# nfc_with_data_transfer_no_accel_2_0.net
KiCad netlist of a schematic drawn in EAGLE
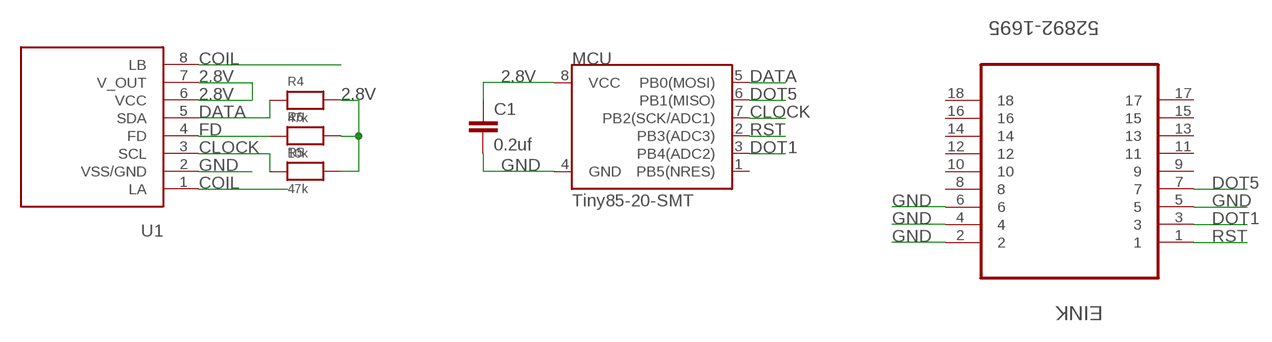
[diagram p0: schematic, sheet 1]

(export (version "E")
  (design (tool "Eeschema 10.0.6"))
  (components
    (comp (ref "C1")
      (value "0.2uf")
      (footprint "eagle-import:1206")
      (libsource (lib "eagle-import") (part "CAP1206"))
    )
    (comp (ref "EINK")
      (value "52892-1695")
      (footprint "eagle-import:MOLEX_52892-1695")
      (libsource (lib "eagle-import") (part "52892-1695"))
    )
    (comp (ref "MCU")
      (value "Tiny85-20-SMT")
      (footprint "eagle-import:SO08-EIAJ")
      (libsource (lib "eagle-import") (part "ATTINY45TINY85-20-SMT"))
    )
    (comp (ref "R4")
      (value "47k")
      (footprint "eagle-import:0603")
      (libsource (lib "eagle-import") (part "RESISTOR0603"))
    )
    (comp (ref "R5")
      (value "47k")
      (footprint "eagle-import:0603")
      (libsource (lib "eagle-import") (part "RESISTOR0603"))
    )
    (comp (ref "R6")
      (value "10k")
      (footprint "eagle-import:0603")
      (libsource (lib "eagle-import") (part "RESISTOR0603"))
    )
    (comp (ref "U1")
      (value "NT3H1101")
      (footprint "eagle-import:NT3H1101")
      (libsource (lib "eagle-import") (part "NT3H1101"))
    )
  )
  (nets
    (net (code "1") (name "/2.8V") (class "Default")
      (node (ref "C1") (pin "1") (pinfunction "1_1") (pintype "passive"))
      (node (ref "MCU") (pin "8") (pinfunction "VCC_8") (pintype "bidirectional"))
      (node (ref "R4") (pin "2") (pinfunction "2_2") (pintype "passive"))
      (node (ref "R5") (pin "2") (pinfunction "2_2") (pintype "passive"))
      (node (ref "R6") (pin "2") (pinfunction "2_2") (pintype "passive"))
      (node (ref "U1") (pin "6") (pinfunction "VCC_6") (pintype "power_in"))
      (node (ref "U1") (pin "7") (pinfunction "V_OUT_7") (pintype "power_in"))
    )
    (net (code "2") (name "/CLOCK") (class "Default")
      (node (ref "MCU") (pin "7") (pinfunction "PB2(SCK/ADC1)_7") (pintype "bidirectional"))
      (node (ref "R5") (pin "1") (pinfunction "1_1") (pintype "passive"))
      (node (ref "U1") (pin "3") (pinfunction "SCL_3") (pintype "bidirectional"))
    )
    (net (code "3") (name "/COIL") (class "Default")
      (node (ref "U1") (pin "1") (pinfunction "LA_1") (pintype "bidirectional"))
      (node (ref "U1") (pin "8") (pinfunction "LB_8") (pintype "bidirectional"))
    )
    (net (code "4") (name "/DATA") (class "Default")
      (node (ref "MCU") (pin "5") (pinfunction "PB0(MOSI)_5") (pintype "bidirectional"))
      (node (ref "R4") (pin "1") (pinfunction "1_1") (pintype "passive"))
      (node (ref "U1") (pin "5") (pinfunction "SDA_5") (pintype "bidirectional"))
    )
    (net (code "5") (name "/DOT1") (class "Default")
      (node (ref "EINK") (pin "3") (pinfunction "3_3") (pintype "passive"))
      (node (ref "MCU") (pin "3") (pinfunction "PB4(ADC2)_3") (pintype "bidirectional"))
    )
    (net (code "6") (name "/DOT5") (class "Default")
      (node (ref "EINK") (pin "7") (pinfunction "7_7") (pintype "passive"))
      (node (ref "MCU") (pin "6") (pinfunction "PB1(MISO)_6") (pintype "bidirectional"))
    )
    (net (code "7") (name "/FD") (class "Default")
      (node (ref "R6") (pin "1") (pinfunction "1_1") (pintype "passive"))
      (node (ref "U1") (pin "4") (pinfunction "FD_4") (pintype "bidirectional"))
    )
    (net (code "8") (name "/GND") (class "Default")
      (node (ref "C1") (pin "2") (pinfunction "2_2") (pintype "passive"))
      (node (ref "EINK") (pin "2") (pinfunction "2_2") (pintype "passive"))
      (node (ref "EINK") (pin "4") (pinfunction "4_4") (pintype "passive"))
      (node (ref "EINK") (pin "5") (pinfunction "5_5") (pintype "passive"))
      (node (ref "EINK") (pin "6") (pinfunction "6_6") (pintype "passive"))
      (node (ref "MCU") (pin "4") (pinfunction "GND_4") (pintype "bidirectional"))
      (node (ref "U1") (pin "2") (pinfunction "VSS/GND_2") (pintype "power_in"))
    )
    (net (code "9") (name "/RST") (class "Default")
      (node (ref "EINK") (pin "1") (pinfunction "1_1") (pintype "passive"))
      (node (ref "MCU") (pin "2") (pinfunction "PB3(ADC3)_2") (pintype "bidirectional"))
    )
    (net (code "10") (name "unconnected-(EINK-Pad8)") (class "Default")
      (node (ref "EINK") (pin "8") (pinfunction "8_8") (pintype "passive"))
    )
    (net (code "11") (name "unconnected-(EINK-Pad9)") (class "Default")
      (node (ref "EINK") (pin "9") (pinfunction "9_9") (pintype "passive"))
    )
    (net (code "12") (name "unconnected-(EINK-Pad10)") (class "Default")
      (node (ref "EINK") (pin "10") (pinfunction "10_10") (pintype "passive"))
    )
    (net (code "13") (name "unconnected-(EINK-Pad11)") (class "Default")
      (node (ref "EINK") (pin "11") (pinfunction "11_11") (pintype "passive"))
    )
    (net (code "14") (name "unconnected-(EINK-Pad12)") (class "Default")
      (node (ref "EINK") (pin "12") (pinfunction "12_12") (pintype "passive"))
    )
    (net (code "15") (name "unconnected-(EINK-Pad13)") (class "Default")
      (node (ref "EINK") (pin "13") (pinfunction "13_13") (pintype "passive"))
    )
    (net (code "16") (name "unconnected-(EINK-Pad14)") (class "Default")
      (node (ref "EINK") (pin "14") (pinfunction "14_14") (pintype "passive"))
    )
    (net (code "17") (name "unconnected-(EINK-Pad15)") (class "Default")
      (node (ref "EINK") (pin "15") (pinfunction "15_15") (pintype "passive"))
    )
    (net (code "18") (name "unconnected-(EINK-Pad16)") (class "Default")
      (node (ref "EINK") (pin "16") (pinfunction "16_16") (pintype "passive"))
    )
    (net (code "19") (name "unconnected-(EINK-Pad17)") (class "Default")
      (node (ref "EINK") (pin "17") (pinfunction "17_17") (pintype "passive"))
    )
    (net (code "20") (name "unconnected-(EINK-Pad18)") (class "Default")
      (node (ref "EINK") (pin "18") (pinfunction "18_18") (pintype "passive"))
    )
    (net (code "21") (name "unconnected-(MCU-PB5(NRES)-Pad1)") (class "Default")
      (node (ref "MCU") (pin "1") (pinfunction "PB5(NRES)_1") (pintype "bidirectional"))
    )
  )
)
